# Current-LoadSwitches_5V0.net
KiCad netlist of a schematic drawn in Altium Designer
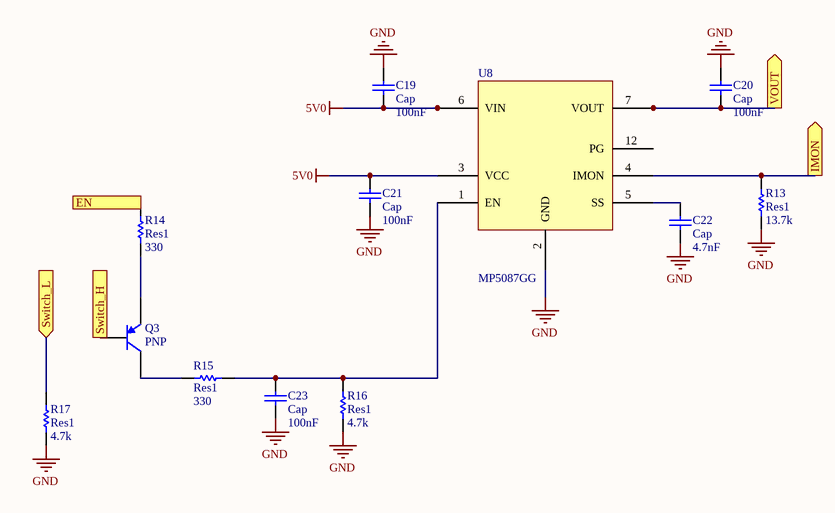
[diagram p0: Current-LoadSwitches 5V0.SchDoc]

(export (version "E")
  (design (tool "Eeschema 10.0.6"))
  (components
    (comp (ref "C19")
      (value "Cap")
      (footprint "0402-A")
      (description "Capacitor")
      (fields (field (name "ALTIUM_VALUE") "100nF") (field (name "PUBLISHER") "Altium Limited"))
      (libsource (lib "Miscellaneous Devices") (part "Cap"))
    )
    (comp (ref "C20")
      (value "Cap")
      (footprint "0402-A")
      (description "Capacitor")
      (fields (field (name "ALTIUM_VALUE") "100nF") (field (name "PUBLISHER") "Altium Limited"))
      (libsource (lib "Miscellaneous Devices") (part "Cap"))
    )
    (comp (ref "C21")
      (value "Cap")
      (footprint "0402-A")
      (description "Capacitor")
      (fields (field (name "ALTIUM_VALUE") "100nF") (field (name "PUBLISHER") "Altium Limited"))
      (libsource (lib "Miscellaneous Devices") (part "Cap"))
    )
    (comp (ref "C22")
      (value "Cap")
      (footprint "0402-A")
      (description "Capacitor")
      (fields (field (name "ALTIUM_VALUE") "4.7nF") (field (name "PUBLISHER") "Altium Limited"))
      (libsource (lib "Miscellaneous Devices") (part "Cap"))
    )
    (comp (ref "C23")
      (value "Cap")
      (footprint "0402-A")
      (description "Capacitor")
      (fields (field (name "ALTIUM_VALUE") "100nF") (field (name "PUBLISHER") "Altium Limited"))
      (libsource (lib "Miscellaneous Devices") (part "Cap"))
    )
    (comp (ref "Q3")
      (value "PNP")
      (footprint "SOT-23B_N")
      (description "PNP Bipolar Transistor")
      (fields (field (name "PUBLISHER") "Altium Limited"))
      (libsource (lib "Miscellaneous Devices") (part "PNP"))
    )
    (comp (ref "R13")
      (value "Res1")
      (footprint "0402-A")
      (description "Resistor")
      (fields (field (name "ALTIUM_VALUE") "13.7k") (field (name "PUBLISHER") "Altium Limited"))
      (libsource (lib "Miscellaneous Devices") (part "Res1"))
    )
    (comp (ref "R14")
      (value "Res1")
      (footprint "0402-A")
      (description "Resistor")
      (fields (field (name "ALTIUM_VALUE") "330") (field (name "PUBLISHER") "Altium Limited"))
      (libsource (lib "Miscellaneous Devices") (part "Res1"))
    )
    (comp (ref "R15")
      (value "Res1")
      (footprint "0402-A")
      (description "Resistor")
      (fields (field (name "ALTIUM_VALUE") "330") (field (name "PUBLISHER") "Altium Limited"))
      (libsource (lib "Miscellaneous Devices") (part "Res1"))
    )
    (comp (ref "R16")
      (value "Res1")
      (footprint "0402-A")
      (description "Resistor")
      (fields (field (name "ALTIUM_VALUE") "4.7k") (field (name "PUBLISHER") "Altium Limited"))
      (libsource (lib "Miscellaneous Devices") (part "Res1"))
    )
    (comp (ref "R17")
      (value "Res1")
      (footprint "0402-A")
      (description "Resistor")
      (fields (field (name "ALTIUM_VALUE") "4.7k") (field (name "PUBLISHER") "Altium Limited"))
      (libsource (lib "Miscellaneous Devices") (part "Res1"))
    )
    (comp (ref "U8")
      (value "MP5087GG")
      (footprint "MP5087GG-Z")
      (libsource (lib "MP5087GG-Z") (part "Component_1"))
    )
  )
  (nets
    (net (code "1") (name "/EN") (class "Default")
      (node (ref "R14") (pin "2") (pinfunction "2_2") (pintype "passive"))
    )
    (net (code "2") (name "/IMON") (class "Default")
      (node (ref "R13") (pin "2") (pinfunction "2_2") (pintype "passive"))
      (node (ref "U8") (pin "4") (pinfunction "IMON_4") (pintype "passive"))
    )
    (net (code "3") (name "/Switch_H") (class "Default")
      (node (ref "Q3") (pin "2") (pinfunction "B_2") (pintype "passive"))
    )
    (net (code "4") (name "/Switch_L") (class "Default")
      (node (ref "R17") (pin "2") (pinfunction "2_2") (pintype "passive"))
    )
    (net (code "5") (name "/VOUT") (class "Default")
      (node (ref "C20") (pin "1") (pinfunction "1_1") (pintype "passive"))
      (node (ref "U8") (pin "10") (pinfunction "VOUT_10") (pintype "passive"))
      (node (ref "U8") (pin "7") (pinfunction "VOUT_7") (pintype "passive"))
      (node (ref "U8") (pin "8") (pinfunction "VOUT_8") (pintype "passive"))
      (node (ref "U8") (pin "9") (pinfunction "VOUT_9") (pintype "passive"))
    )
    (net (code "6") (name "5V0") (class "Default")
      (node (ref "C19") (pin "1") (pinfunction "1_1") (pintype "passive"))
      (node (ref "C21") (pin "2") (pinfunction "2_2") (pintype "passive"))
      (node (ref "U8") (pin "11") (pinfunction "VOUT_11") (pintype "passive"))
      (node (ref "U8") (pin "3") (pinfunction "VCC_3") (pintype "passive"))
      (node (ref "U8") (pin "6") (pinfunction "VIN_6") (pintype "passive"))
    )
    (net (code "7") (name "GND") (class "Default")
      (node (ref "C19") (pin "2") (pinfunction "2_2") (pintype "passive"))
      (node (ref "C20") (pin "2") (pinfunction "2_2") (pintype "passive"))
      (node (ref "C21") (pin "1") (pinfunction "1_1") (pintype "passive"))
      (node (ref "C22") (pin "1") (pinfunction "1_1") (pintype "passive"))
      (node (ref "C23") (pin "1") (pinfunction "1_1") (pintype "passive"))
      (node (ref "R13") (pin "1") (pinfunction "1_1") (pintype "passive"))
      (node (ref "R16") (pin "1") (pinfunction "1_1") (pintype "passive"))
      (node (ref "R17") (pin "1") (pinfunction "1_1") (pintype "passive"))
      (node (ref "U8") (pin "2") (pinfunction "GND_2") (pintype "passive"))
    )
    (net (code "8") (name "Net-(Q3-C)") (class "Default")
      (node (ref "Q3") (pin "1") (pinfunction "C_1") (pintype "passive"))
      (node (ref "R15") (pin "1") (pinfunction "1_1") (pintype "passive"))
    )
    (net (code "9") (name "Net-(Q3-E)") (class "Default")
      (node (ref "Q3") (pin "3") (pinfunction "E_3") (pintype "passive"))
      (node (ref "R14") (pin "1") (pinfunction "1_1") (pintype "passive"))
    )
    (net (code "10") (name "Net-(U8-EN)") (class "Default")
      (node (ref "C23") (pin "2") (pinfunction "2_2") (pintype "passive"))
      (node (ref "R15") (pin "2") (pinfunction "2_2") (pintype "passive"))
      (node (ref "R16") (pin "2") (pinfunction "2_2") (pintype "passive"))
      (node (ref "U8") (pin "1") (pinfunction "EN_1") (pintype "passive"))
    )
    (net (code "11") (name "Net-(U8-SS)") (class "Default")
      (node (ref "C22") (pin "2") (pinfunction "2_2") (pintype "passive"))
      (node (ref "U8") (pin "5") (pinfunction "SS_5") (pintype "passive"))
    )
    (net (code "12") (name "unconnected-(U8-PG-Pad12)") (class "Default")
      (node (ref "U8") (pin "12") (pinfunction "PG_12") (pintype "passive"))
    )
  )
)
